# MicroController.net
KiCad netlist of a schematic drawn in Altium Designer
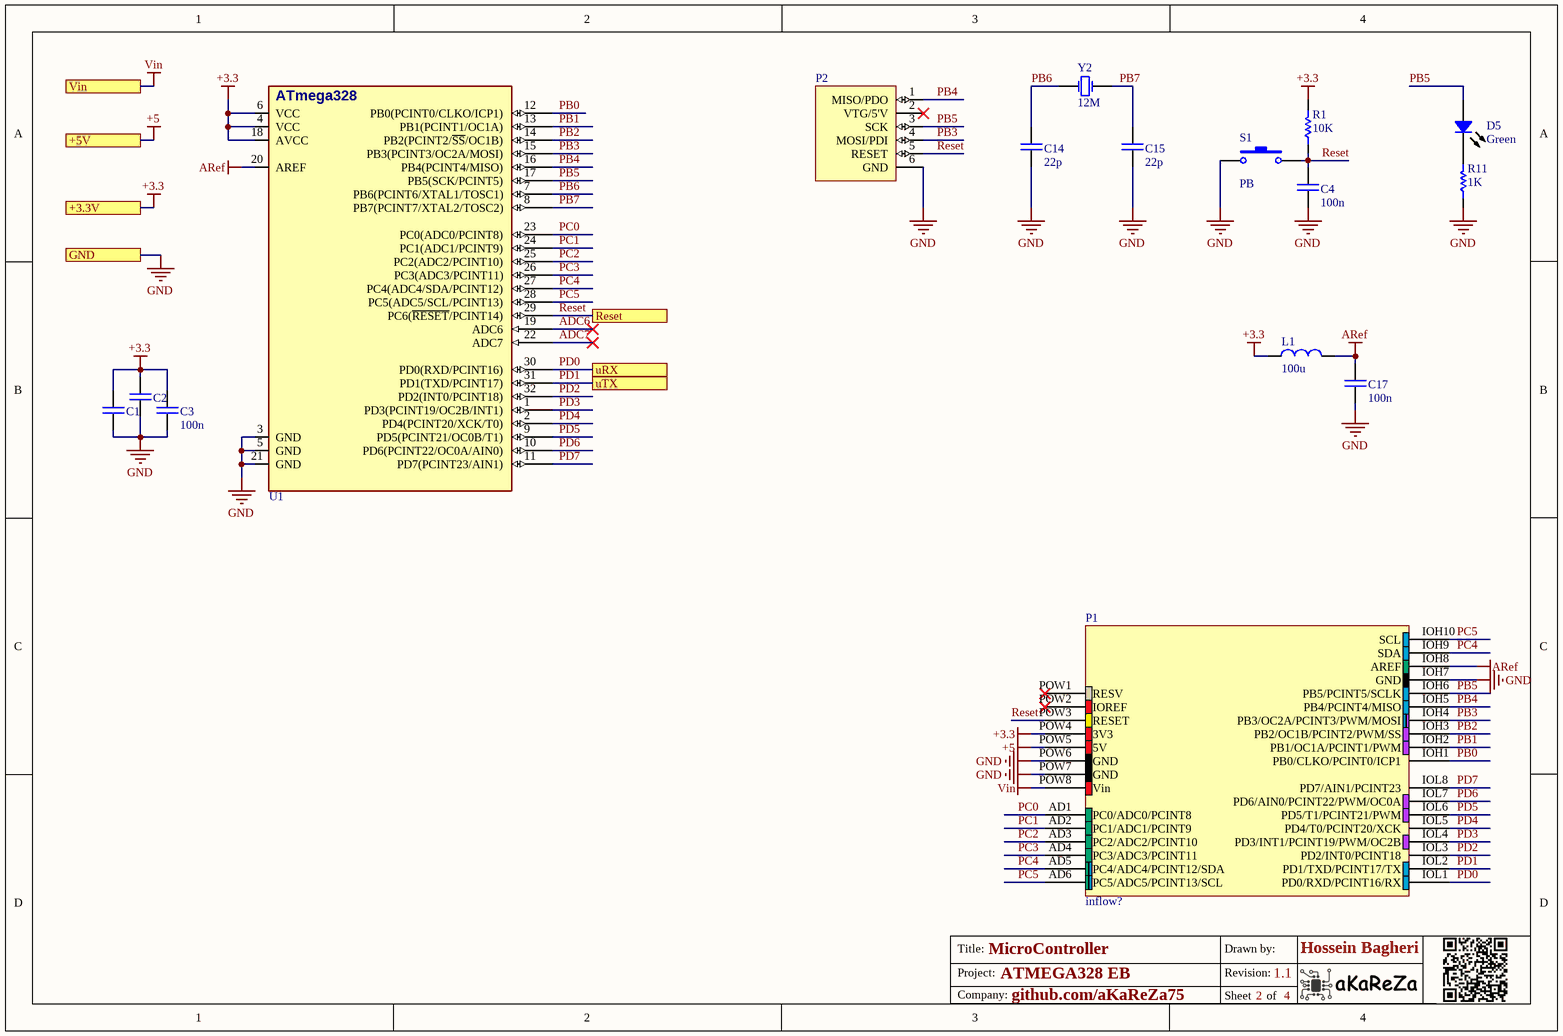
[diagram p0: MicroController.SchDoc]

(export (version "E")
  (design (tool "Eeschema 10.0.6"))
  (components
    (comp (ref "C1")
      (value "100n")
      (footprint "CAP 0805/2012")
      (description "Bipolar ceramic capacitor SMD")
      (fields (field (name "VALIDATION") "Valid"))
      (libsource (lib "aKaReZa") (part "Cap_Multi_SMD_100nF_0805"))
    )
    (comp (ref "C2")
      (value "100n")
      (footprint "CAP 0805/2012")
      (description "Bipolar ceramic capacitor SMD")
      (fields (field (name "VALIDATION") "Valid"))
      (libsource (lib "aKaReZa") (part "Cap_Multi_SMD_100nF_0805"))
    )
    (comp (ref "C3")
      (value "100n")
      (footprint "CAP 0805/2012")
      (description "Bipolar ceramic capacitor SMD")
      (fields (field (name "VALIDATION") "Valid"))
      (libsource (lib "aKaReZa") (part "Cap_Multi_SMD_100nF_0805"))
    )
    (comp (ref "C4")
      (value "100n")
      (footprint "CAP 0805/2012")
      (description "Bipolar ceramic capacitor SMD")
      (fields (field (name "VALIDATION") "Valid"))
      (libsource (lib "aKaReZa") (part "Cap_Multi_SMD_100nF_0805"))
    )
    (comp (ref "C14")
      (value "22p")
      (footprint "CAP 0805/2012")
      (description "Bipolar ceramic capacitor SMD")
      (fields (field (name "VALIDATION") "Valid"))
      (libsource (lib "aKaReZa") (part "Cap_Multi_SMD_0805"))
    )
    (comp (ref "C15")
      (value "22p")
      (footprint "CAP 0805/2012")
      (description "Bipolar ceramic capacitor SMD")
      (fields (field (name "VALIDATION") "Valid"))
      (libsource (lib "aKaReZa") (part "Cap_Multi_SMD_0805"))
    )
    (comp (ref "C17")
      (value "100n")
      (footprint "CAP 0805/2012")
      (description "Bipolar ceramic capacitor SMD")
      (fields (field (name "VALIDATION") "Valid"))
      (libsource (lib "aKaReZa") (part "Cap_Multi_SMD_100nF_0805"))
    )
    (comp (ref "D5")
      (value "Green")
      (footprint "LED 0805/2012 GREEN")
      (description "LED")
      (fields (field (name "VALIDATION") "Valid"))
      (libsource (lib "aKaReZa") (part "Semi_LED_SMD"))
    )
    (comp (ref "L1")
      (value "100u")
      (footprint "IND0805")
      (description "Inductor")
      (fields (field (name "VALIDATION") "Valid"))
      (libsource (lib "aKaReZa") (part "Ind_SMD_0805"))
    )
    (comp (ref "P1")
      (value "UNO")
      (footprint "ARDUINO_UNO_CONNECTOR")
      (description "Arduino UNO Connector")
      (fields (field (name "INFLOW") "inflow?") (field (name "VALIDATION") "NT"))
      (libsource (lib "aKaReZa") (part "Con_Arduino_UNO_Con"))
    )
    (comp (ref "P2")
      (value "3x2")
      (footprint "IDC_2X3")
      (description "6 Pin Standard ISP Header For MKII")
      (fields (field (name "VALIDATION") "NT"))
      (libsource (lib "aKaReZa") (part "Con_Prog_MKII_ISP"))
    )
    (comp (ref "R1")
      (value "10K")
      (footprint "RES 0805 (2012X06L)")
      (description "Resistor")
      (fields (field (name "VALIDATION") "Valid"))
      (libsource (lib "aKaReZa") (part "Res_SMD_0805"))
    )
    (comp (ref "R11")
      (value "1K")
      (footprint "RES 0805 (2012X06L)")
      (description "Resistor")
      (fields (field (name "VALIDATION") "Valid"))
      (libsource (lib "aKaReZa") (part "Res_SMD_0805"))
    )
    (comp (ref "S1")
      (value "PB")
      (footprint "SW_PB_SMD_2PIN_SPST_6X3X2")
      (description "SMT Tactile ‎Switch")
      (fields (field (name "VALIDATION") "Valid"))
      (libsource (lib "aKaReZa") (part "SW_PushButton_2_SMD"))
    )
    (comp (ref "U1")
      (value "ATmega328P")
      (footprint "ATMEGA328")
      (description "8-Bit AVR Microcontroller with 32K Bytes of In-System Programmable Flash Memory")
      (fields (field (name "VALIDATION") "Valid"))
      (libsource (lib "aKaReZa") (part "IC_MCU_ATmega328P_SMD"))
    )
    (comp (ref "Y2")
      (value "12M")
      (footprint "Crystal SMD")
      (description "Crystal Oscillator")
      (fields (field (name "VALIDATION") "Valid"))
      (libsource (lib "aKaReZa") (part "Other_Elec_Xtal_SMD"))
    )
  )
  (nets
    (net (code "1") (name "+3.3") (class "Default")
      (node (ref "C1") (pin "1") (pinfunction "1_1") (pintype "passive"))
      (node (ref "C2") (pin "1") (pinfunction "1_1") (pintype "passive"))
      (node (ref "C3") (pin "1") (pinfunction "1_1") (pintype "passive"))
      (node (ref "L1") (pin "1") (pinfunction "1_1") (pintype "passive"))
      (node (ref "P1") (pin "POW4") (pinfunction "3V3_POW4") (pintype "passive"))
      (node (ref "R1") (pin "2") (pinfunction "2_2") (pintype "passive"))
      (node (ref "U1") (pin "18") (pinfunction "AVCC_18") (pintype "power_in"))
      (node (ref "U1") (pin "4") (pinfunction "VCC_4") (pintype "power_in"))
      (node (ref "U1") (pin "6") (pinfunction "VCC_6") (pintype "power_in"))
    )
    (net (code "2") (name "+5") (class "Default")
      (node (ref "P1") (pin "POW5") (pinfunction "5V_POW5") (pintype "passive"))
    )
    (net (code "3") (name "/ADC6") (class "Default")
      (node (ref "U1") (pin "19") (pinfunction "ADC6_19") (pintype "input+no_connect"))
    )
    (net (code "4") (name "/ADC7") (class "Default")
      (node (ref "U1") (pin "22") (pinfunction "ADC7_22") (pintype "input+no_connect"))
    )
    (net (code "5") (name "/PB0") (class "Default")
      (node (ref "P1") (pin "IOH1") (pinfunction "PB0/CLKO/PCINT0/ICP1_IOH1") (pintype "passive"))
      (node (ref "U1") (pin "12") (pinfunction "PB0(PCINT0/CLKO/ICP1)_12") (pintype "bidirectional"))
    )
    (net (code "6") (name "/PB1") (class "Default")
      (node (ref "P1") (pin "IOH2") (pinfunction "PB1/OC1A/PCINT1/PWM_IOH2") (pintype "passive"))
      (node (ref "U1") (pin "13") (pinfunction "PB1(PCINT1/OC1A)_13") (pintype "bidirectional"))
    )
    (net (code "7") (name "/PB2") (class "Default")
      (node (ref "P1") (pin "IOH3") (pinfunction "PB2/OC1B/PCINT2/PWM/SS_IOH3") (pintype "passive"))
      (node (ref "U1") (pin "14") (pinfunction "PB2(PCINT2/~{SS}/OC1B)_14") (pintype "bidirectional"))
    )
    (net (code "8") (name "/PB3") (class "Default")
      (node (ref "P1") (pin "IOH4") (pinfunction "PB3/OC2A/PCINT3/PWM/MOSI_IOH4") (pintype "passive"))
      (node (ref "P2") (pin "4") (pinfunction "MOSI/PDI_4") (pintype "bidirectional"))
      (node (ref "U1") (pin "15") (pinfunction "PB3(PCINT3/OC2A/MOSI)_15") (pintype "bidirectional"))
    )
    (net (code "9") (name "/PB4") (class "Default")
      (node (ref "P1") (pin "IOH5") (pinfunction "PB4/PCINT4/MISO_IOH5") (pintype "passive"))
      (node (ref "P2") (pin "1") (pinfunction "MISO/PDO_1") (pintype "bidirectional"))
      (node (ref "U1") (pin "16") (pinfunction "PB4(PCINT4/MISO)_16") (pintype "bidirectional"))
    )
    (net (code "10") (name "/PB5") (class "Default")
      (node (ref "D5") (pin "1") (pinfunction "1_1") (pintype "passive"))
      (node (ref "P1") (pin "IOH6") (pinfunction "PB5/PCINT5/SCLK_IOH6") (pintype "passive"))
      (node (ref "P2") (pin "3") (pinfunction "SCK_3") (pintype "bidirectional"))
      (node (ref "U1") (pin "17") (pinfunction "PB5(SCK/PCINT5)_17") (pintype "bidirectional"))
    )
    (net (code "11") (name "/PB6") (class "Default")
      (node (ref "C14") (pin "1") (pinfunction "1_1") (pintype "passive"))
      (node (ref "U1") (pin "7") (pinfunction "PB6(PCINT6/XTAL1/TOSC1)_7") (pintype "bidirectional"))
      (node (ref "Y2") (pin "1") (pinfunction "OSC1_1") (pintype "passive"))
    )
    (net (code "12") (name "/PB7") (class "Default")
      (node (ref "C15") (pin "1") (pinfunction "1_1") (pintype "passive"))
      (node (ref "U1") (pin "8") (pinfunction "PB7(PCINT7/XTAL2/TOSC2)_8") (pintype "bidirectional"))
      (node (ref "Y2") (pin "2") (pinfunction "OSC2_2") (pintype "passive"))
    )
    (net (code "13") (name "/PC0") (class "Default")
      (node (ref "P1") (pin "AD1") (pinfunction "PC0/ADC0/PCINT8_AD1") (pintype "passive"))
      (node (ref "U1") (pin "23") (pinfunction "PC0(ADC0/PCINT8)_23") (pintype "bidirectional"))
    )
    (net (code "14") (name "/PC1") (class "Default")
      (node (ref "P1") (pin "AD2") (pinfunction "PC1/ADC1/PCINT9_AD2") (pintype "passive"))
      (node (ref "U1") (pin "24") (pinfunction "PC1(ADC1/PCINT9)_24") (pintype "bidirectional"))
    )
    (net (code "15") (name "/PC2") (class "Default")
      (node (ref "P1") (pin "AD3") (pinfunction "PC2/ADC2/PCINT10_AD3") (pintype "passive"))
      (node (ref "U1") (pin "25") (pinfunction "PC2(ADC2/PCINT10)_25") (pintype "bidirectional"))
    )
    (net (code "16") (name "/PC3") (class "Default")
      (node (ref "P1") (pin "AD4") (pinfunction "PC3/ADC3/PCINT11_AD4") (pintype "passive"))
      (node (ref "U1") (pin "26") (pinfunction "PC3(ADC3/PCINT11)_26") (pintype "bidirectional"))
    )
    (net (code "17") (name "/PC4") (class "Default")
      (node (ref "P1") (pin "AD5") (pinfunction "PC4/ADC4/PCINT12/SDA_AD5") (pintype "passive"))
      (node (ref "P1") (pin "IOH9") (pinfunction "SDA_IOH9") (pintype "passive"))
      (node (ref "U1") (pin "27") (pinfunction "PC4(ADC4/SDA/PCINT12)_27") (pintype "bidirectional"))
    )
    (net (code "18") (name "/PC5") (class "Default")
      (node (ref "P1") (pin "AD6") (pinfunction "PC5/ADC5/PCINT13/SCL_AD6") (pintype "passive"))
      (node (ref "P1") (pin "IOH10") (pinfunction "SCL_IOH10") (pintype "passive"))
      (node (ref "U1") (pin "28") (pinfunction "PC5(ADC5/SCL/PCINT13)_28") (pintype "bidirectional"))
    )
    (net (code "19") (name "/PD0") (class "Default")
      (node (ref "P1") (pin "IOL1") (pinfunction "PD0/RXD/PCINT16/RX_IOL1") (pintype "passive"))
      (node (ref "U1") (pin "30") (pinfunction "PD0(RXD/PCINT16)_30") (pintype "bidirectional"))
    )
    (net (code "20") (name "/PD1") (class "Default")
      (node (ref "P1") (pin "IOL2") (pinfunction "PD1/TXD/PCINT17/TX_IOL2") (pintype "passive"))
      (node (ref "U1") (pin "31") (pinfunction "PD1(TXD/PCINT17)_31") (pintype "bidirectional"))
    )
    (net (code "21") (name "/PD2") (class "Default")
      (node (ref "P1") (pin "IOL3") (pinfunction "PD2/INT0/PCINT18_IOL3") (pintype "passive"))
      (node (ref "U1") (pin "32") (pinfunction "PD2(INT0/PCINT18)_32") (pintype "bidirectional"))
    )
    (net (code "22") (name "/PD3") (class "Default")
      (node (ref "P1") (pin "IOL4") (pinfunction "PD3/INT1/PCINT19/PWM/OC2B_IOL4") (pintype "passive"))
      (node (ref "U1") (pin "1") (pinfunction "PD3(PCINT19/OC2B/INT1)_1") (pintype "bidirectional"))
    )
    (net (code "23") (name "/PD4") (class "Default")
      (node (ref "P1") (pin "IOL5") (pinfunction "PD4/T0/PCINT20/XCK_IOL5") (pintype "passive"))
      (node (ref "U1") (pin "2") (pinfunction "PD4(PCINT20/XCK/T0)_2") (pintype "bidirectional"))
    )
    (net (code "24") (name "/PD5") (class "Default")
      (node (ref "P1") (pin "IOL6") (pinfunction "PD5/T1/PCINT21/PWM_IOL6") (pintype "passive"))
      (node (ref "U1") (pin "9") (pinfunction "PD5(PCINT21/OC0B/T1)_9") (pintype "bidirectional"))
    )
    (net (code "25") (name "/PD6") (class "Default")
      (node (ref "P1") (pin "IOL7") (pinfunction "PD6/AIN0/PCINT22/PWM/OC0A_IOL7") (pintype "passive"))
      (node (ref "U1") (pin "10") (pinfunction "PD6(PCINT22/OC0A/AIN0)_10") (pintype "bidirectional"))
    )
    (net (code "26") (name "/PD7") (class "Default")
      (node (ref "P1") (pin "IOL8") (pinfunction "PD7/AIN1/PCINT23_IOL8") (pintype "passive"))
      (node (ref "U1") (pin "11") (pinfunction "PD7(PCINT23/AIN1)_11") (pintype "bidirectional"))
    )
    (net (code "27") (name "/Reset") (class "Default")
      (node (ref "C4") (pin "1") (pinfunction "1_1") (pintype "passive"))
      (node (ref "P1") (pin "POW3") (pinfunction "RESET_POW3") (pintype "passive"))
      (node (ref "P2") (pin "5") (pinfunction "RESET_5") (pintype "bidirectional"))
      (node (ref "R1") (pin "1") (pinfunction "1_1") (pintype "passive"))
      (node (ref "S1") (pin "2") (pinfunction "2_2") (pintype "passive"))
      (node (ref "U1") (pin "29") (pinfunction "PC6(~{RESET}/PCINT14)_29") (pintype "bidirectional"))
    )
    (net (code "28") (name "ARef") (class "Default")
      (node (ref "C17") (pin "1") (pinfunction "1_1") (pintype "passive"))
      (node (ref "L1") (pin "2") (pinfunction "2_2") (pintype "passive"))
      (node (ref "P1") (pin "IOH8") (pinfunction "AREF_IOH8") (pintype "passive"))
      (node (ref "U1") (pin "20") (pinfunction "AREF_20") (pintype "passive"))
    )
    (net (code "29") (name "GND") (class "Default")
      (node (ref "C1") (pin "2") (pinfunction "2_2") (pintype "passive"))
      (node (ref "C14") (pin "2") (pinfunction "2_2") (pintype "passive"))
      (node (ref "C15") (pin "2") (pinfunction "2_2") (pintype "passive"))
      (node (ref "C17") (pin "2") (pinfunction "2_2") (pintype "passive"))
      (node (ref "C2") (pin "2") (pinfunction "2_2") (pintype "passive"))
      (node (ref "C3") (pin "2") (pinfunction "2_2") (pintype "passive"))
      (node (ref "C4") (pin "2") (pinfunction "2_2") (pintype "passive"))
      (node (ref "P1") (pin "IOH7") (pinfunction "GND_IOH7") (pintype "passive"))
      (node (ref "P1") (pin "POW6") (pinfunction "GND_POW6") (pintype "passive"))
      (node (ref "P1") (pin "POW7") (pinfunction "GND_POW7") (pintype "passive"))
      (node (ref "P2") (pin "6") (pinfunction "GND_6") (pintype "passive"))
      (node (ref "R11") (pin "1") (pinfunction "1_1") (pintype "passive"))
      (node (ref "S1") (pin "1") (pinfunction "1_1") (pintype "passive"))
      (node (ref "U1") (pin "21") (pinfunction "GND_21") (pintype "power_in"))
      (node (ref "U1") (pin "3") (pinfunction "GND_3") (pintype "power_in"))
      (node (ref "U1") (pin "5") (pinfunction "GND_5") (pintype "power_in"))
    )
    (net (code "30") (name "Net-(D5-Pad2)") (class "Default")
      (node (ref "D5") (pin "2") (pinfunction "2_2") (pintype "passive"))
      (node (ref "R11") (pin "2") (pinfunction "2_2") (pintype "passive"))
    )
    (net (code "31") (name "Vin") (class "Default")
      (node (ref "P1") (pin "POW8") (pinfunction "Vin_POW8") (pintype "passive"))
    )
    (net (code "32") (name "unconnected-(P1-IOREF-PadPOW2)") (class "Default")
      (node (ref "P1") (pin "POW2") (pinfunction "IOREF_POW2") (pintype "passive+no_connect"))
    )
    (net (code "33") (name "unconnected-(P1-RESV-PadPOW1)") (class "Default")
      (node (ref "P1") (pin "POW1") (pinfunction "RESV_POW1") (pintype "passive+no_connect"))
    )
    (net (code "34") (name "unconnected-(P2-VTG{slash}5'V-Pad2)") (class "Default")
      (node (ref "P2") (pin "2") (pinfunction "VTG/5'V_2") (pintype "passive+no_connect"))
    )
  )
)
